# jtag-adapter-3-5.net
KiCad netlist of a schematic drawn in EAGLE
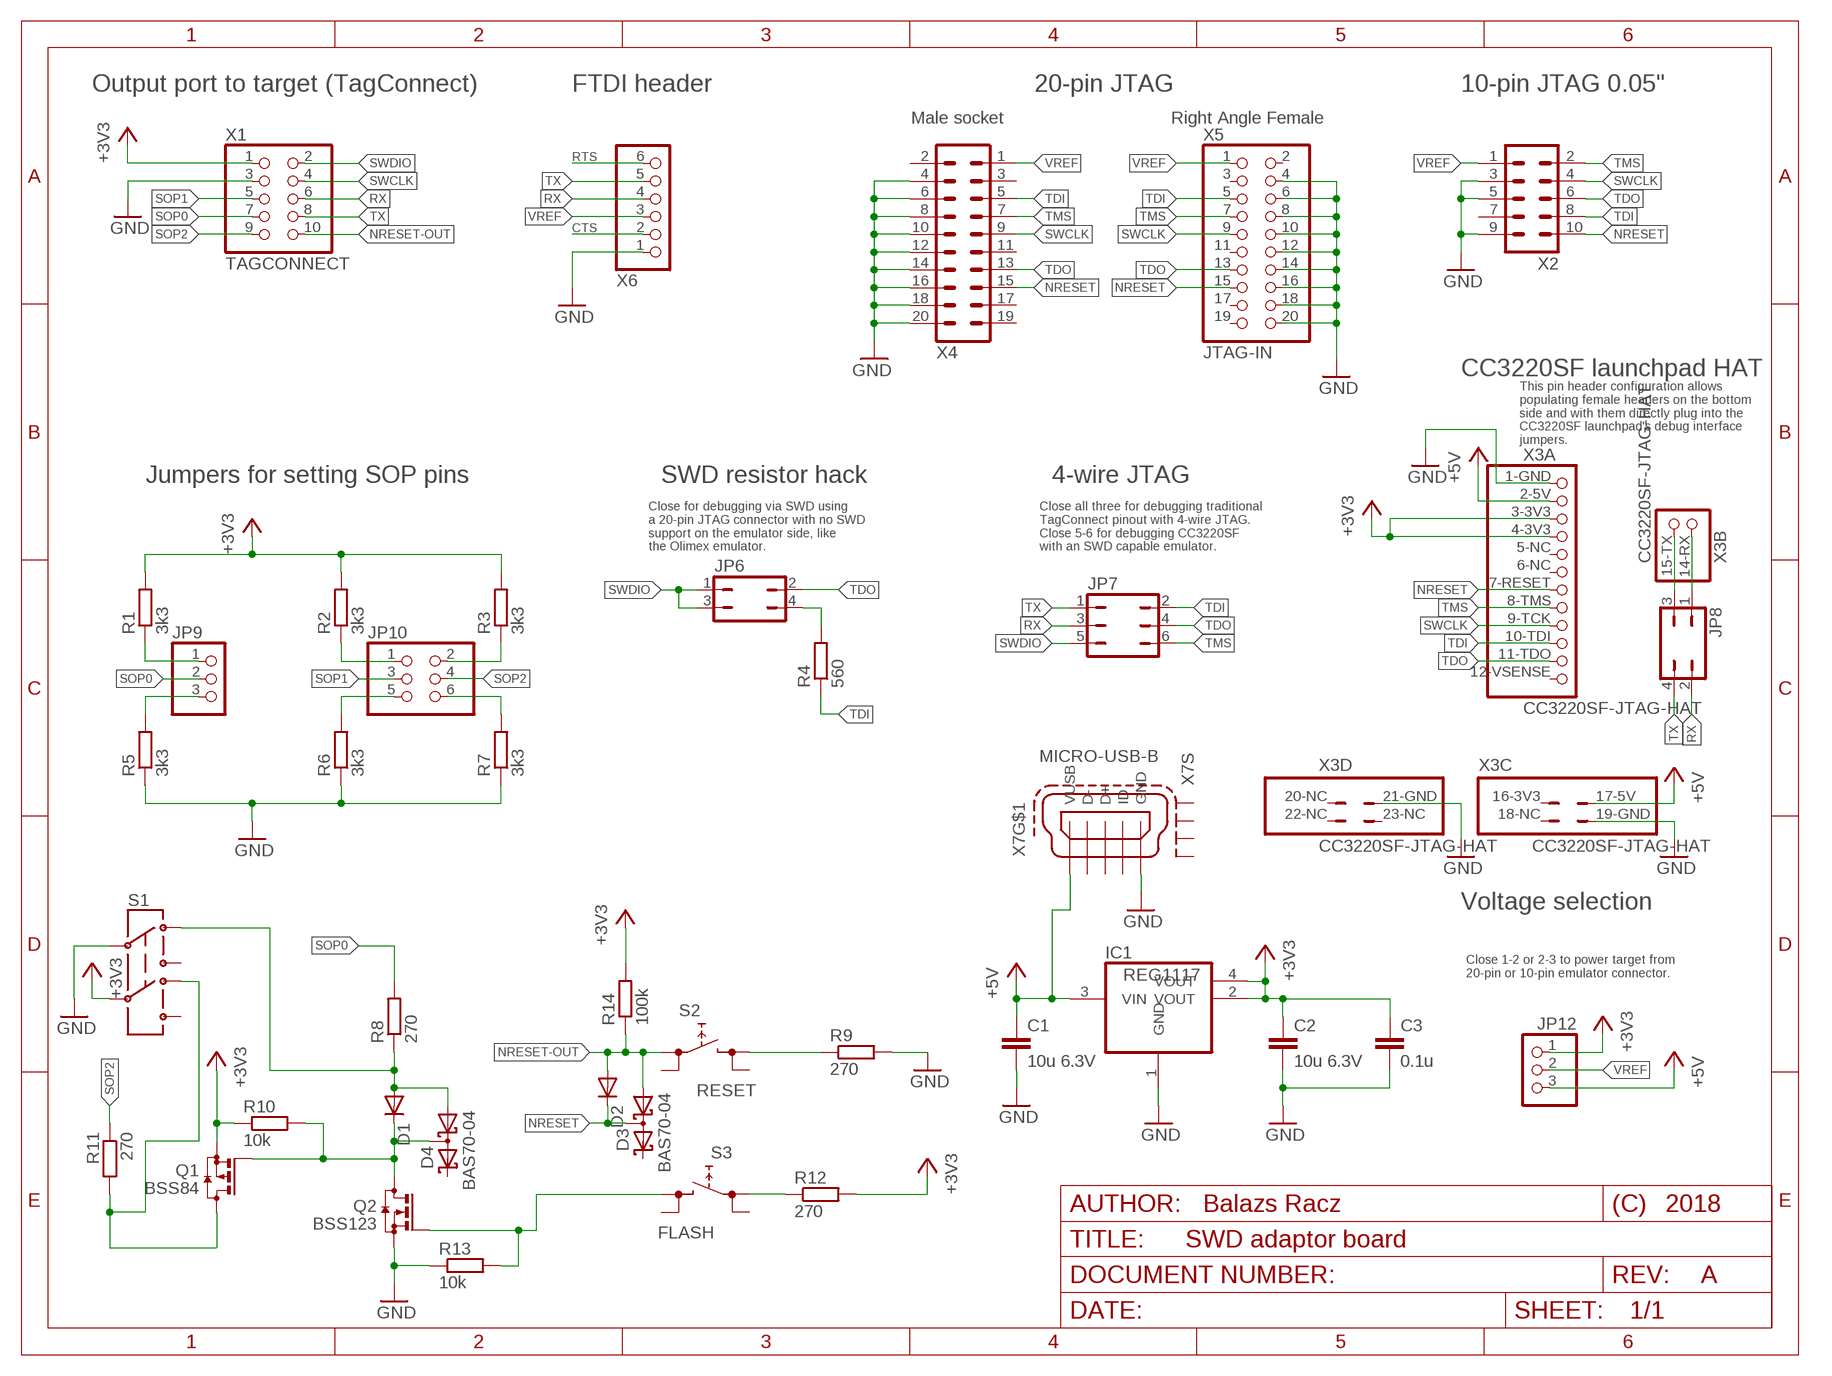
[diagram p0: schematic, sheet 1]

(export (version "E")
  (design (tool "Eeschema 10.0.6"))
  (components
    (comp (ref "C1")
      (value "10u 6.3V")
      (footprint "eagle-import:C0603K")
      (libsource (lib "eagle-import") (part "C-EUC0603K"))
    )
    (comp (ref "C2")
      (value "10u 6.3V")
      (footprint "eagle-import:C0603K")
      (libsource (lib "eagle-import") (part "C-EUC0603K"))
    )
    (comp (ref "C3")
      (value "0.1u")
      (footprint "eagle-import:C0603K")
      (libsource (lib "eagle-import") (part "C-EUC0603K"))
    )
    (comp (ref "D1")
      (value "DIODE-MINIMELF")
      (footprint "eagle-import:MINIMELF")
      (libsource (lib "eagle-import") (part "DIODE-MINIMELF"))
    )
    (comp (ref "D2")
      (value "DIODE-MINIMELF")
      (footprint "eagle-import:MINIMELF")
      (libsource (lib "eagle-import") (part "DIODE-MINIMELF"))
    )
    (comp (ref "D3")
      (value "BAS70-04")
      (footprint "eagle-import:SOT23")
      (libsource (lib "eagle-import") (part "BAS70-04"))
    )
    (comp (ref "D4")
      (value "BAS70-04")
      (footprint "eagle-import:SOT23")
      (libsource (lib "eagle-import") (part "BAS70-04"))
    )
    (comp (ref "IC1")
      (value "REG1117")
      (footprint "eagle-import:SOT223")
      (libsource (lib "eagle-import") (part "REG1117"))
    )
    (comp (ref "JP6")
      (value "JP2Q")
      (footprint "eagle-import:JP2Q")
      (libsource (lib "eagle-import") (part "JP2Q"))
    )
    (comp (ref "JP7")
      (value "JP3Q")
      (footprint "eagle-import:JP3Q")
      (libsource (lib "eagle-import") (part "JP3Q"))
    )
    (comp (ref "JP8")
      (value "JP2Q")
      (footprint "eagle-import:JP2Q")
      (libsource (lib "eagle-import") (part "JP2Q"))
    )
    (comp (ref "JP9")
      (value "PINHD-1X3")
      (footprint "eagle-import:1X03")
      (libsource (lib "eagle-import") (part "PINHD-1X3"))
    )
    (comp (ref "JP10")
      (value "PINHD-2X3")
      (footprint "eagle-import:2X03")
      (libsource (lib "eagle-import") (part "PINHD-2X3"))
    )
    (comp (ref "JP12")
      (value "PINHD-1X3")
      (footprint "eagle-import:1X03")
      (libsource (lib "eagle-import") (part "PINHD-1X3"))
    )
    (comp (ref "Q1")
      (value "BSS84")
      (footprint "eagle-import:SOT23")
      (libsource (lib "eagle-import") (part "BSS84"))
    )
    (comp (ref "Q2")
      (value "BSS123")
      (footprint "eagle-import:SOT23")
      (libsource (lib "eagle-import") (part "BSS123"))
    )
    (comp (ref "R1")
      (value "3k3")
      (footprint "eagle-import:R0805")
      (libsource (lib "eagle-import") (part "R-EU_R0805"))
    )
    (comp (ref "R2")
      (value "3k3")
      (footprint "eagle-import:R0805")
      (libsource (lib "eagle-import") (part "R-EU_R0805"))
    )
    (comp (ref "R3")
      (value "3k3")
      (footprint "eagle-import:R0805")
      (libsource (lib "eagle-import") (part "R-EU_R0805"))
    )
    (comp (ref "R4")
      (value "560")
      (footprint "eagle-import:R0805")
      (libsource (lib "eagle-import") (part "R-EU_R0805"))
    )
    (comp (ref "R5")
      (value "3k3")
      (footprint "eagle-import:R0805")
      (libsource (lib "eagle-import") (part "R-EU_R0805"))
    )
    (comp (ref "R6")
      (value "3k3")
      (footprint "eagle-import:R0805")
      (libsource (lib "eagle-import") (part "R-EU_R0805"))
    )
    (comp (ref "R7")
      (value "3k3")
      (footprint "eagle-import:R0805")
      (libsource (lib "eagle-import") (part "R-EU_R0805"))
    )
    (comp (ref "R8")
      (value "270")
      (footprint "eagle-import:R0805")
      (libsource (lib "eagle-import") (part "R-EU_R0805"))
    )
    (comp (ref "R9")
      (value "270")
      (footprint "eagle-import:R0805")
      (libsource (lib "eagle-import") (part "R-EU_R0805"))
    )
    (comp (ref "R10")
      (value "10k")
      (footprint "eagle-import:R0805")
      (libsource (lib "eagle-import") (part "R-EU_R0805"))
    )
    (comp (ref "R11")
      (value "270")
      (footprint "eagle-import:R0805")
      (libsource (lib "eagle-import") (part "R-EU_R0805"))
    )
    (comp (ref "R12")
      (value "270")
      (footprint "eagle-import:R0805")
      (libsource (lib "eagle-import") (part "R-EU_R0805"))
    )
    (comp (ref "R13")
      (value "10k")
      (footprint "eagle-import:R0805")
      (libsource (lib "eagle-import") (part "R-EU_R0805"))
    )
    (comp (ref "R14")
      (value "100k")
      (footprint "eagle-import:R0805")
      (libsource (lib "eagle-import") (part "R-EU_R0805"))
    )
    (comp (ref "S1")
      (value "SWITCH-DPDTJS202011CQN")
      (footprint "eagle-import:DPDT-2.5X3.2MM")
      (libsource (lib "eagle-import") (part "SWITCH-DPDTJS202011CQN"))
    )
    (comp (ref "S2")
      (value "RESET")
      (footprint "eagle-import:TACTSW-6X6")
      (libsource (lib "eagle-import") (part "TACTSW-6X6S"))
    )
    (comp (ref "S3")
      (value "FLASH")
      (footprint "eagle-import:TACTSW-6X6")
      (libsource (lib "eagle-import") (part "TACTSW-6X6S"))
    )
    (comp (ref "X1")
      (value "TAGCONNECT")
      (footprint "eagle-import:CON10M")
      (libsource (lib "eagle-import") (part "PINHD-2X5CN"))
    )
    (comp (ref "X2")
      (value "MA05-2_0.05X0.05")
      (footprint "eagle-import:MA05-2_0.05_X_0.05")
      (libsource (lib "eagle-import") (part "MA05-2_0.05X0.05"))
    )
    (comp (ref "X3")
      (value "CC3220SF-JTAG-HAT")
      (footprint "eagle-import:JTAG-LAUNCHPAD-3220SF")
      (libsource (lib "eagle-import") (part "CC3220SF-JTAG-HAT"))
    )
    (comp (ref "X4")
      (value "MA10-2S")
      (footprint "eagle-import:MA10-2-SHROUDED")
      (libsource (lib "eagle-import") (part "MA10-2S"))
    )
    (comp (ref "X5")
      (value "JTAG-IN")
      (footprint "eagle-import:2X10")
      (libsource (lib "eagle-import") (part "PINHD-2X10"))
    )
    (comp (ref "X6")
      (value "PINHD-1X6")
      (footprint "eagle-import:1X06")
      (libsource (lib "eagle-import") (part "PINHD-1X6"))
    )
    (comp (ref "X7")
      (value "MICRO-USB-B")
      (footprint "eagle-import:MICRO-B-PAC")
      (libsource (lib "eagle-import") (part "MICRO-USB-B"))
    )
  )
  (nets
    (net (code "1") (name "+3V3") (class "Default")
      (node (ref "C2") (pin "1") (pinfunction "1_1") (pintype "passive"))
      (node (ref "C3") (pin "1") (pinfunction "1_1") (pintype "passive"))
      (node (ref "IC1") (pin "2") (pinfunction "VOUT_2") (pintype "output"))
      (node (ref "IC1") (pin "4") (pinfunction "VOUT_4") (pintype "output"))
      (node (ref "JP12") (pin "1") (pinfunction "1_1") (pintype "passive"))
      (node (ref "Q1") (pin "2") (pinfunction "S_2") (pintype "passive"))
      (node (ref "R1") (pin "2") (pinfunction "2_2") (pintype "passive"))
      (node (ref "R10") (pin "1") (pinfunction "1_1") (pintype "passive"))
      (node (ref "R12") (pin "2") (pinfunction "2_2") (pintype "passive"))
      (node (ref "R14") (pin "2") (pinfunction "2_2") (pintype "passive"))
      (node (ref "R2") (pin "2") (pinfunction "2_2") (pintype "passive"))
      (node (ref "R3") (pin "2") (pinfunction "2_2") (pintype "passive"))
      (node (ref "S1") (pin "5") (pinfunction "2C_5") (pintype "bidirectional"))
      (node (ref "X1") (pin "1") (pinfunction "1_1") (pintype "passive"))
      (node (ref "X3") (pin "3-3V3") (pinfunction "3_3-3V3") (pintype "passive"))
      (node (ref "X3") (pin "4-3V3") (pinfunction "4_4-3V3") (pintype "passive"))
    )
    (net (code "2") (name "+5V") (class "Default")
      (node (ref "C1") (pin "1") (pinfunction "1_1") (pintype "passive"))
      (node (ref "IC1") (pin "3") (pinfunction "VIN_3") (pintype "input"))
      (node (ref "JP12") (pin "3") (pinfunction "3_3") (pintype "passive"))
      (node (ref "X3") (pin "17-5V") (pinfunction "2_17-5V") (pintype "passive"))
      (node (ref "X3") (pin "2-5V") (pinfunction "2_2-5V") (pintype "passive"))
      (node (ref "X7") (pin "1") (pinfunction "VUSB_1") (pintype "passive"))
    )
    (net (code "3") (name "/CTS") (class "Default")
      (node (ref "X6") (pin "2") (pinfunction "2_2") (pintype "passive"))
    )
    (net (code "4") (name "/RTS") (class "Default")
      (node (ref "X6") (pin "6") (pinfunction "6_6") (pintype "passive"))
    )
    (net (code "5") (name "GND") (class "Default")
      (node (ref "C1") (pin "2") (pinfunction "2_2") (pintype "passive"))
      (node (ref "C2") (pin "2") (pinfunction "2_2") (pintype "passive"))
      (node (ref "C3") (pin "2") (pinfunction "2_2") (pintype "passive"))
      (node (ref "IC1") (pin "1") (pinfunction "GND_1") (pintype "power_in"))
      (node (ref "Q2") (pin "2") (pinfunction "S_2") (pintype "passive"))
      (node (ref "R13") (pin "1") (pinfunction "1_1") (pintype "passive"))
      (node (ref "R5") (pin "1") (pinfunction "1_1") (pintype "passive"))
      (node (ref "R6") (pin "1") (pinfunction "1_1") (pintype "passive"))
      (node (ref "R7") (pin "1") (pinfunction "1_1") (pintype "passive"))
      (node (ref "R9") (pin "2") (pinfunction "2_2") (pintype "passive"))
      (node (ref "S1") (pin "2") (pinfunction "1C_2") (pintype "bidirectional"))
      (node (ref "X1") (pin "3") (pinfunction "3_3") (pintype "passive"))
      (node (ref "X2") (pin "3") (pinfunction "3_3") (pintype "passive"))
      (node (ref "X2") (pin "5") (pinfunction "5_5") (pintype "passive"))
      (node (ref "X2") (pin "9") (pinfunction "9_9") (pintype "passive"))
      (node (ref "X3") (pin "1-GND") (pinfunction "1_1-GND") (pintype "passive"))
      (node (ref "X3") (pin "19-GND") (pinfunction "4_19-GND") (pintype "passive"))
      (node (ref "X3") (pin "21-GND") (pinfunction "2_21-GND") (pintype "passive"))
      (node (ref "X4") (pin "10") (pinfunction "10_10") (pintype "passive"))
      (node (ref "X4") (pin "12") (pinfunction "12_12") (pintype "passive"))
      (node (ref "X4") (pin "14") (pinfunction "14_14") (pintype "passive"))
      (node (ref "X4") (pin "16") (pinfunction "16_16") (pintype "passive"))
      (node (ref "X4") (pin "18") (pinfunction "18_18") (pintype "passive"))
      (node (ref "X4") (pin "20") (pinfunction "20_20") (pintype "passive"))
      (node (ref "X4") (pin "4") (pinfunction "4_4") (pintype "passive"))
      (node (ref "X4") (pin "6") (pinfunction "6_6") (pintype "passive"))
      (node (ref "X4") (pin "8") (pinfunction "8_8") (pintype "passive"))
      (node (ref "X5") (pin "10") (pinfunction "10_10") (pintype "passive"))
      (node (ref "X5") (pin "12") (pinfunction "12_12") (pintype "passive"))
      (node (ref "X5") (pin "14") (pinfunction "14_14") (pintype "passive"))
      (node (ref "X5") (pin "16") (pinfunction "16_16") (pintype "passive"))
      (node (ref "X5") (pin "18") (pinfunction "18_18") (pintype "passive"))
      (node (ref "X5") (pin "20") (pinfunction "20_20") (pintype "passive"))
      (node (ref "X5") (pin "4") (pinfunction "4_4") (pintype "passive"))
      (node (ref "X5") (pin "6") (pinfunction "6_6") (pintype "passive"))
      (node (ref "X5") (pin "8") (pinfunction "8_8") (pintype "passive"))
      (node (ref "X6") (pin "1") (pinfunction "1_1") (pintype "passive"))
      (node (ref "X7") (pin "5") (pinfunction "GND_5") (pintype "passive"))
    )
    (net (code "6") (name "NRESET") (class "Default")
      (node (ref "D2") (pin "C") (pinfunction "C_C") (pintype "passive"))
      (node (ref "D3") (pin "3") (pinfunction "C1A2_3") (pintype "passive"))
      (node (ref "X2") (pin "10") (pinfunction "10_10") (pintype "passive"))
      (node (ref "X3") (pin "7-RESET") (pinfunction "7_7-RESET") (pintype "passive"))
      (node (ref "X4") (pin "15") (pinfunction "15_15") (pintype "passive"))
      (node (ref "X5") (pin "15") (pinfunction "15_15") (pintype "passive"))
    )
    (net (code "7") (name "NRESET-OUT") (class "Default")
      (node (ref "D2") (pin "A") (pinfunction "A_A") (pintype "passive"))
      (node (ref "D3") (pin "1") (pinfunction "A1_1") (pintype "passive"))
      (node (ref "R14") (pin "1") (pinfunction "1_1") (pintype "passive"))
      (node (ref "S2") (pin "1") (pinfunction "1.1_1") (pintype "passive"))
      (node (ref "X1") (pin "10") (pinfunction "10_10") (pintype "passive"))
    )
    (net (code "8") (name "Net-(D4-A1)") (class "Default")
      (node (ref "D1") (pin "A") (pinfunction "A_A") (pintype "passive"))
      (node (ref "D4") (pin "1") (pinfunction "A1_1") (pintype "passive"))
      (node (ref "R8") (pin "1") (pinfunction "1_1") (pintype "passive"))
      (node (ref "S1") (pin "1") (pinfunction "1A_1") (pintype "bidirectional"))
    )
    (net (code "9") (name "Net-(D4-C1A2)") (class "Default")
      (node (ref "D1") (pin "C") (pinfunction "C_C") (pintype "passive"))
      (node (ref "D4") (pin "3") (pinfunction "C1A2_3") (pintype "passive"))
      (node (ref "Q1") (pin "1") (pinfunction "G_1") (pintype "passive"))
      (node (ref "Q2") (pin "3") (pinfunction "D_3") (pintype "passive"))
      (node (ref "R10") (pin "2") (pinfunction "2_2") (pintype "passive"))
    )
    (net (code "10") (name "Net-(JP6-Pad4)") (class "Default")
      (node (ref "JP6") (pin "4") (pinfunction "4_4") (pintype "passive"))
      (node (ref "R4") (pin "2") (pinfunction "2_2") (pintype "passive"))
    )
    (net (code "11") (name "Net-(JP9-Pad1)") (class "Default")
      (node (ref "JP9") (pin "1") (pinfunction "1_1") (pintype "passive"))
      (node (ref "R1") (pin "1") (pinfunction "1_1") (pintype "passive"))
    )
    (net (code "12") (name "Net-(JP9-Pad3)") (class "Default")
      (node (ref "JP9") (pin "3") (pinfunction "3_3") (pintype "passive"))
      (node (ref "R5") (pin "2") (pinfunction "2_2") (pintype "passive"))
    )
    (net (code "13") (name "Net-(JP10-Pad1)") (class "Default")
      (node (ref "JP10") (pin "1") (pinfunction "1_1") (pintype "passive"))
      (node (ref "R2") (pin "1") (pinfunction "1_1") (pintype "passive"))
    )
    (net (code "14") (name "Net-(JP10-Pad2)") (class "Default")
      (node (ref "JP10") (pin "2") (pinfunction "2_2") (pintype "passive"))
      (node (ref "R3") (pin "1") (pinfunction "1_1") (pintype "passive"))
    )
    (net (code "15") (name "Net-(JP10-Pad5)") (class "Default")
      (node (ref "JP10") (pin "5") (pinfunction "5_5") (pintype "passive"))
      (node (ref "R6") (pin "2") (pinfunction "2_2") (pintype "passive"))
    )
    (net (code "16") (name "Net-(JP10-Pad6)") (class "Default")
      (node (ref "JP10") (pin "6") (pinfunction "6_6") (pintype "passive"))
      (node (ref "R7") (pin "2") (pinfunction "2_2") (pintype "passive"))
    )
    (net (code "17") (name "Net-(Q1-D)") (class "Default")
      (node (ref "Q1") (pin "3") (pinfunction "D_3") (pintype "passive"))
      (node (ref "R11") (pin "2") (pinfunction "2_2") (pintype "passive"))
      (node (ref "S1") (pin "4") (pinfunction "2A_4") (pintype "bidirectional"))
    )
    (net (code "18") (name "Net-(Q2-G)") (class "Default")
      (node (ref "Q2") (pin "1") (pinfunction "G_1") (pintype "passive"))
      (node (ref "R13") (pin "2") (pinfunction "2_2") (pintype "passive"))
      (node (ref "S3") (pin "3") (pinfunction "2.1_3") (pintype "passive"))
    )
    (net (code "19") (name "Net-(S2-2.1)") (class "Default")
      (node (ref "R9") (pin "1") (pinfunction "1_1") (pintype "passive"))
      (node (ref "S2") (pin "3") (pinfunction "2.1_3") (pintype "passive"))
    )
    (net (code "20") (name "Net-(S3-1.1)") (class "Default")
      (node (ref "R12") (pin "1") (pinfunction "1_1") (pintype "passive"))
      (node (ref "S3") (pin "1") (pinfunction "1.1_1") (pintype "passive"))
    )
    (net (code "21") (name "Net-(X3B-1)") (class "Default")
      (node (ref "JP8") (pin "1") (pinfunction "1_1") (pintype "passive"))
      (node (ref "X3") (pin "14-RX") (pinfunction "1_14-RX") (pintype "passive"))
    )
    (net (code "22") (name "Net-(X3B-2)") (class "Default")
      (node (ref "JP8") (pin "3") (pinfunction "3_3") (pintype "passive"))
      (node (ref "X3") (pin "15-TX") (pinfunction "2_15-TX") (pintype "passive"))
    )
    (net (code "23") (name "RX") (class "Default")
      (node (ref "JP7") (pin "3") (pinfunction "3_3") (pintype "passive"))
      (node (ref "JP8") (pin "2") (pinfunction "2_2") (pintype "passive"))
      (node (ref "X1") (pin "6") (pinfunction "6_6") (pintype "passive"))
      (node (ref "X6") (pin "4") (pinfunction "4_4") (pintype "passive"))
    )
    (net (code "24") (name "SOP0") (class "Default")
      (node (ref "JP9") (pin "2") (pinfunction "2_2") (pintype "passive"))
      (node (ref "R8") (pin "2") (pinfunction "2_2") (pintype "passive"))
      (node (ref "X1") (pin "7") (pinfunction "7_7") (pintype "passive"))
    )
    (net (code "25") (name "SOP1") (class "Default")
      (node (ref "JP10") (pin "3") (pinfunction "3_3") (pintype "passive"))
      (node (ref "X1") (pin "5") (pinfunction "5_5") (pintype "passive"))
    )
    (net (code "26") (name "SOP2") (class "Default")
      (node (ref "JP10") (pin "4") (pinfunction "4_4") (pintype "passive"))
      (node (ref "R11") (pin "1") (pinfunction "1_1") (pintype "passive"))
      (node (ref "X1") (pin "9") (pinfunction "9_9") (pintype "passive"))
    )
    (net (code "27") (name "SWCLK") (class "Default")
      (node (ref "X1") (pin "4") (pinfunction "4_4") (pintype "passive"))
      (node (ref "X2") (pin "4") (pinfunction "4_4") (pintype "passive"))
      (node (ref "X3") (pin "9-TCK") (pinfunction "9_9-TCK") (pintype "passive"))
      (node (ref "X4") (pin "9") (pinfunction "9_9") (pintype "passive"))
      (node (ref "X5") (pin "9") (pinfunction "9_9") (pintype "passive"))
    )
    (net (code "28") (name "SWDIO") (class "Default")
      (node (ref "JP6") (pin "1") (pinfunction "1_1") (pintype "passive"))
      (node (ref "JP6") (pin "3") (pinfunction "3_3") (pintype "passive"))
      (node (ref "JP7") (pin "5") (pinfunction "5_5") (pintype "passive"))
      (node (ref "X1") (pin "2") (pinfunction "2_2") (pintype "passive"))
    )
    (net (code "29") (name "TDI") (class "Default")
      (node (ref "JP7") (pin "2") (pinfunction "2_2") (pintype "passive"))
      (node (ref "R4") (pin "1") (pinfunction "1_1") (pintype "passive"))
      (node (ref "X2") (pin "8") (pinfunction "8_8") (pintype "passive"))
      (node (ref "X3") (pin "10-TDI") (pinfunction "10_10-TDI") (pintype "passive"))
      (node (ref "X4") (pin "5") (pinfunction "5_5") (pintype "passive"))
      (node (ref "X5") (pin "5") (pinfunction "5_5") (pintype "passive"))
    )
    (net (code "30") (name "TDO") (class "Default")
      (node (ref "JP6") (pin "2") (pinfunction "2_2") (pintype "passive"))
      (node (ref "JP7") (pin "4") (pinfunction "4_4") (pintype "passive"))
      (node (ref "X2") (pin "6") (pinfunction "6_6") (pintype "passive"))
      (node (ref "X3") (pin "11-TDO") (pinfunction "11_11-TDO") (pintype "passive"))
      (node (ref "X4") (pin "13") (pinfunction "13_13") (pintype "passive"))
      (node (ref "X5") (pin "13") (pinfunction "13_13") (pintype "passive"))
    )
    (net (code "31") (name "TMS") (class "Default")
      (node (ref "JP7") (pin "6") (pinfunction "6_6") (pintype "passive"))
      (node (ref "X2") (pin "2") (pinfunction "2_2") (pintype "passive"))
      (node (ref "X3") (pin "8-TMS") (pinfunction "8_8-TMS") (pintype "passive"))
      (node (ref "X4") (pin "7") (pinfunction "7_7") (pintype "passive"))
      (node (ref "X5") (pin "7") (pinfunction "7_7") (pintype "passive"))
    )
    (net (code "32") (name "TX") (class "Default")
      (node (ref "JP7") (pin "1") (pinfunction "1_1") (pintype "passive"))
      (node (ref "JP8") (pin "4") (pinfunction "4_4") (pintype "passive"))
      (node (ref "X1") (pin "8") (pinfunction "8_8") (pintype "passive"))
      (node (ref "X6") (pin "5") (pinfunction "5_5") (pintype "passive"))
    )
    (net (code "33") (name "VREF") (class "Default")
      (node (ref "JP12") (pin "2") (pinfunction "2_2") (pintype "passive"))
      (node (ref "X2") (pin "1") (pinfunction "1_1") (pintype "passive"))
      (node (ref "X4") (pin "1") (pinfunction "1_1") (pintype "passive"))
      (node (ref "X5") (pin "1") (pinfunction "1_1") (pintype "passive"))
      (node (ref "X6") (pin "3") (pinfunction "3_3") (pintype "passive"))
    )
    (net (code "34") (name "unconnected-(D3-C2-Pad2)") (class "Default")
      (node (ref "D3") (pin "2") (pinfunction "C2_2") (pintype "passive"))
    )
    (net (code "35") (name "unconnected-(D4-C2-Pad2)") (class "Default")
      (node (ref "D4") (pin "2") (pinfunction "C2_2") (pintype "passive"))
    )
    (net (code "36") (name "unconnected-(S1-1B-Pad3)") (class "Default")
      (node (ref "S1") (pin "3") (pinfunction "1B_3") (pintype "bidirectional"))
    )
    (net (code "37") (name "unconnected-(S1-2B-Pad6)") (class "Default")
      (node (ref "S1") (pin "6") (pinfunction "2B_6") (pintype "bidirectional"))
    )
    (net (code "38") (name "unconnected-(S2-1.2-Pad2)") (class "Default")
      (node (ref "S2") (pin "2") (pinfunction "1.2_2") (pintype "passive"))
    )
    (net (code "39") (name "unconnected-(S2-2.2-Pad4)") (class "Default")
      (node (ref "S2") (pin "4") (pinfunction "2.2_4") (pintype "passive"))
    )
    (net (code "40") (name "unconnected-(S3-1.2-Pad2)") (class "Default")
      (node (ref "S3") (pin "2") (pinfunction "1.2_2") (pintype "passive"))
    )
    (net (code "41") (name "unconnected-(S3-2.2-Pad4)") (class "Default")
      (node (ref "S3") (pin "4") (pinfunction "2.2_4") (pintype "passive"))
    )
    (net (code "42") (name "unconnected-(X2-Pad7)") (class "Default")
      (node (ref "X2") (pin "7") (pinfunction "7_7") (pintype "passive"))
    )
    (net (code "43") (name "unconnected-(X3A-5-Pad5-NC)") (class "Default")
      (node (ref "X3") (pin "5-NC") (pinfunction "5_5-NC") (pintype "passive"))
    )
    (net (code "44") (name "unconnected-(X3A-6-Pad6-NC)") (class "Default")
      (node (ref "X3") (pin "6-NC") (pinfunction "6_6-NC") (pintype "passive"))
    )
    (net (code "45") (name "unconnected-(X3A-12-Pad12-VSENSE)") (class "Default")
      (node (ref "X3") (pin "12-VSENSE") (pinfunction "12_12-VSENSE") (pintype "passive"))
    )
    (net (code "46") (name "unconnected-(X3C-1-Pad16-3V3)") (class "Default")
      (node (ref "X3") (pin "16-3V3") (pinfunction "1_16-3V3") (pintype "passive"))
    )
    (net (code "47") (name "unconnected-(X3C-3-Pad18-NC)") (class "Default")
      (node (ref "X3") (pin "18-NC") (pinfunction "3_18-NC") (pintype "passive"))
    )
    (net (code "48") (name "unconnected-(X3D-1-Pad20-NC)") (class "Default")
      (node (ref "X3") (pin "20-NC") (pinfunction "1_20-NC") (pintype "passive"))
    )
    (net (code "49") (name "unconnected-(X3D-3-Pad22-NC)") (class "Default")
      (node (ref "X3") (pin "22-NC") (pinfunction "3_22-NC") (pintype "passive"))
    )
    (net (code "50") (name "unconnected-(X3D-4-Pad23-NC)") (class "Default")
      (node (ref "X3") (pin "23-NC") (pinfunction "4_23-NC") (pintype "passive"))
    )
    (net (code "51") (name "unconnected-(X4-Pad2)") (class "Default")
      (node (ref "X4") (pin "2") (pinfunction "2_2") (pintype "passive"))
    )
    (net (code "52") (name "unconnected-(X4-Pad3)") (class "Default")
      (node (ref "X4") (pin "3") (pinfunction "3_3") (pintype "passive"))
    )
    (net (code "53") (name "unconnected-(X4-Pad11)") (class "Default")
      (node (ref "X4") (pin "11") (pinfunction "11_11") (pintype "passive"))
    )
    (net (code "54") (name "unconnected-(X4-Pad17)") (class "Default")
      (node (ref "X4") (pin "17") (pinfunction "17_17") (pintype "passive"))
    )
    (net (code "55") (name "unconnected-(X4-Pad19)") (class "Default")
      (node (ref "X4") (pin "19") (pinfunction "19_19") (pintype "passive"))
    )
    (net (code "56") (name "unconnected-(X5-Pad2)") (class "Default")
      (node (ref "X5") (pin "2") (pinfunction "2_2") (pintype "passive"))
    )
    (net (code "57") (name "unconnected-(X5-Pad3)") (class "Default")
      (node (ref "X5") (pin "3") (pinfunction "3_3") (pintype "passive"))
    )
    (net (code "58") (name "unconnected-(X5-Pad11)") (class "Default")
      (node (ref "X5") (pin "11") (pinfunction "11_11") (pintype "passive"))
    )
    (net (code "59") (name "unconnected-(X5-Pad17)") (class "Default")
      (node (ref "X5") (pin "17") (pinfunction "17_17") (pintype "passive"))
    )
    (net (code "60") (name "unconnected-(X5-Pad19)") (class "Default")
      (node (ref "X5") (pin "19") (pinfunction "19_19") (pintype "passive"))
    )
    (net (code "61") (name "unconnected-(X7A-D+-Pad3)") (class "Default")
      (node (ref "X7") (pin "3") (pinfunction "D+_3") (pintype "passive"))
    )
    (net (code "62") (name "unconnected-(X7A-D--Pad2)") (class "Default")
      (node (ref "X7") (pin "2") (pinfunction "D-_2") (pintype "passive"))
    )
    (net (code "63") (name "unconnected-(X7A-ID-Pad4)") (class "Default")
      (node (ref "X7") (pin "4") (pinfunction "ID_4") (pintype "passive"))
    )
    (net (code "64") (name "unconnected-(X7B-S1-PadM1)") (class "Default")
      (node (ref "X7") (pin "M1") (pinfunction "S1_M1") (pintype "passive"))
    )
    (net (code "65") (name "unconnected-(X7B-S2-PadM2)") (class "Default")
      (node (ref "X7") (pin "M2") (pinfunction "S2_M2") (pintype "passive"))
    )
    (net (code "66") (name "unconnected-(X7B-S3-PadM3)") (class "Default")
      (node (ref "X7") (pin "M3") (pinfunction "S3_M3") (pintype "passive"))
    )
    (net (code "67") (name "unconnected-(X7B-S4-PadM4)") (class "Default")
      (node (ref "X7") (pin "M4") (pinfunction "S4_M4") (pintype "passive"))
    )
  )
)
